# MeteoStation_ETH.net
KiCad netlist of a schematic drawn in Altium Designer
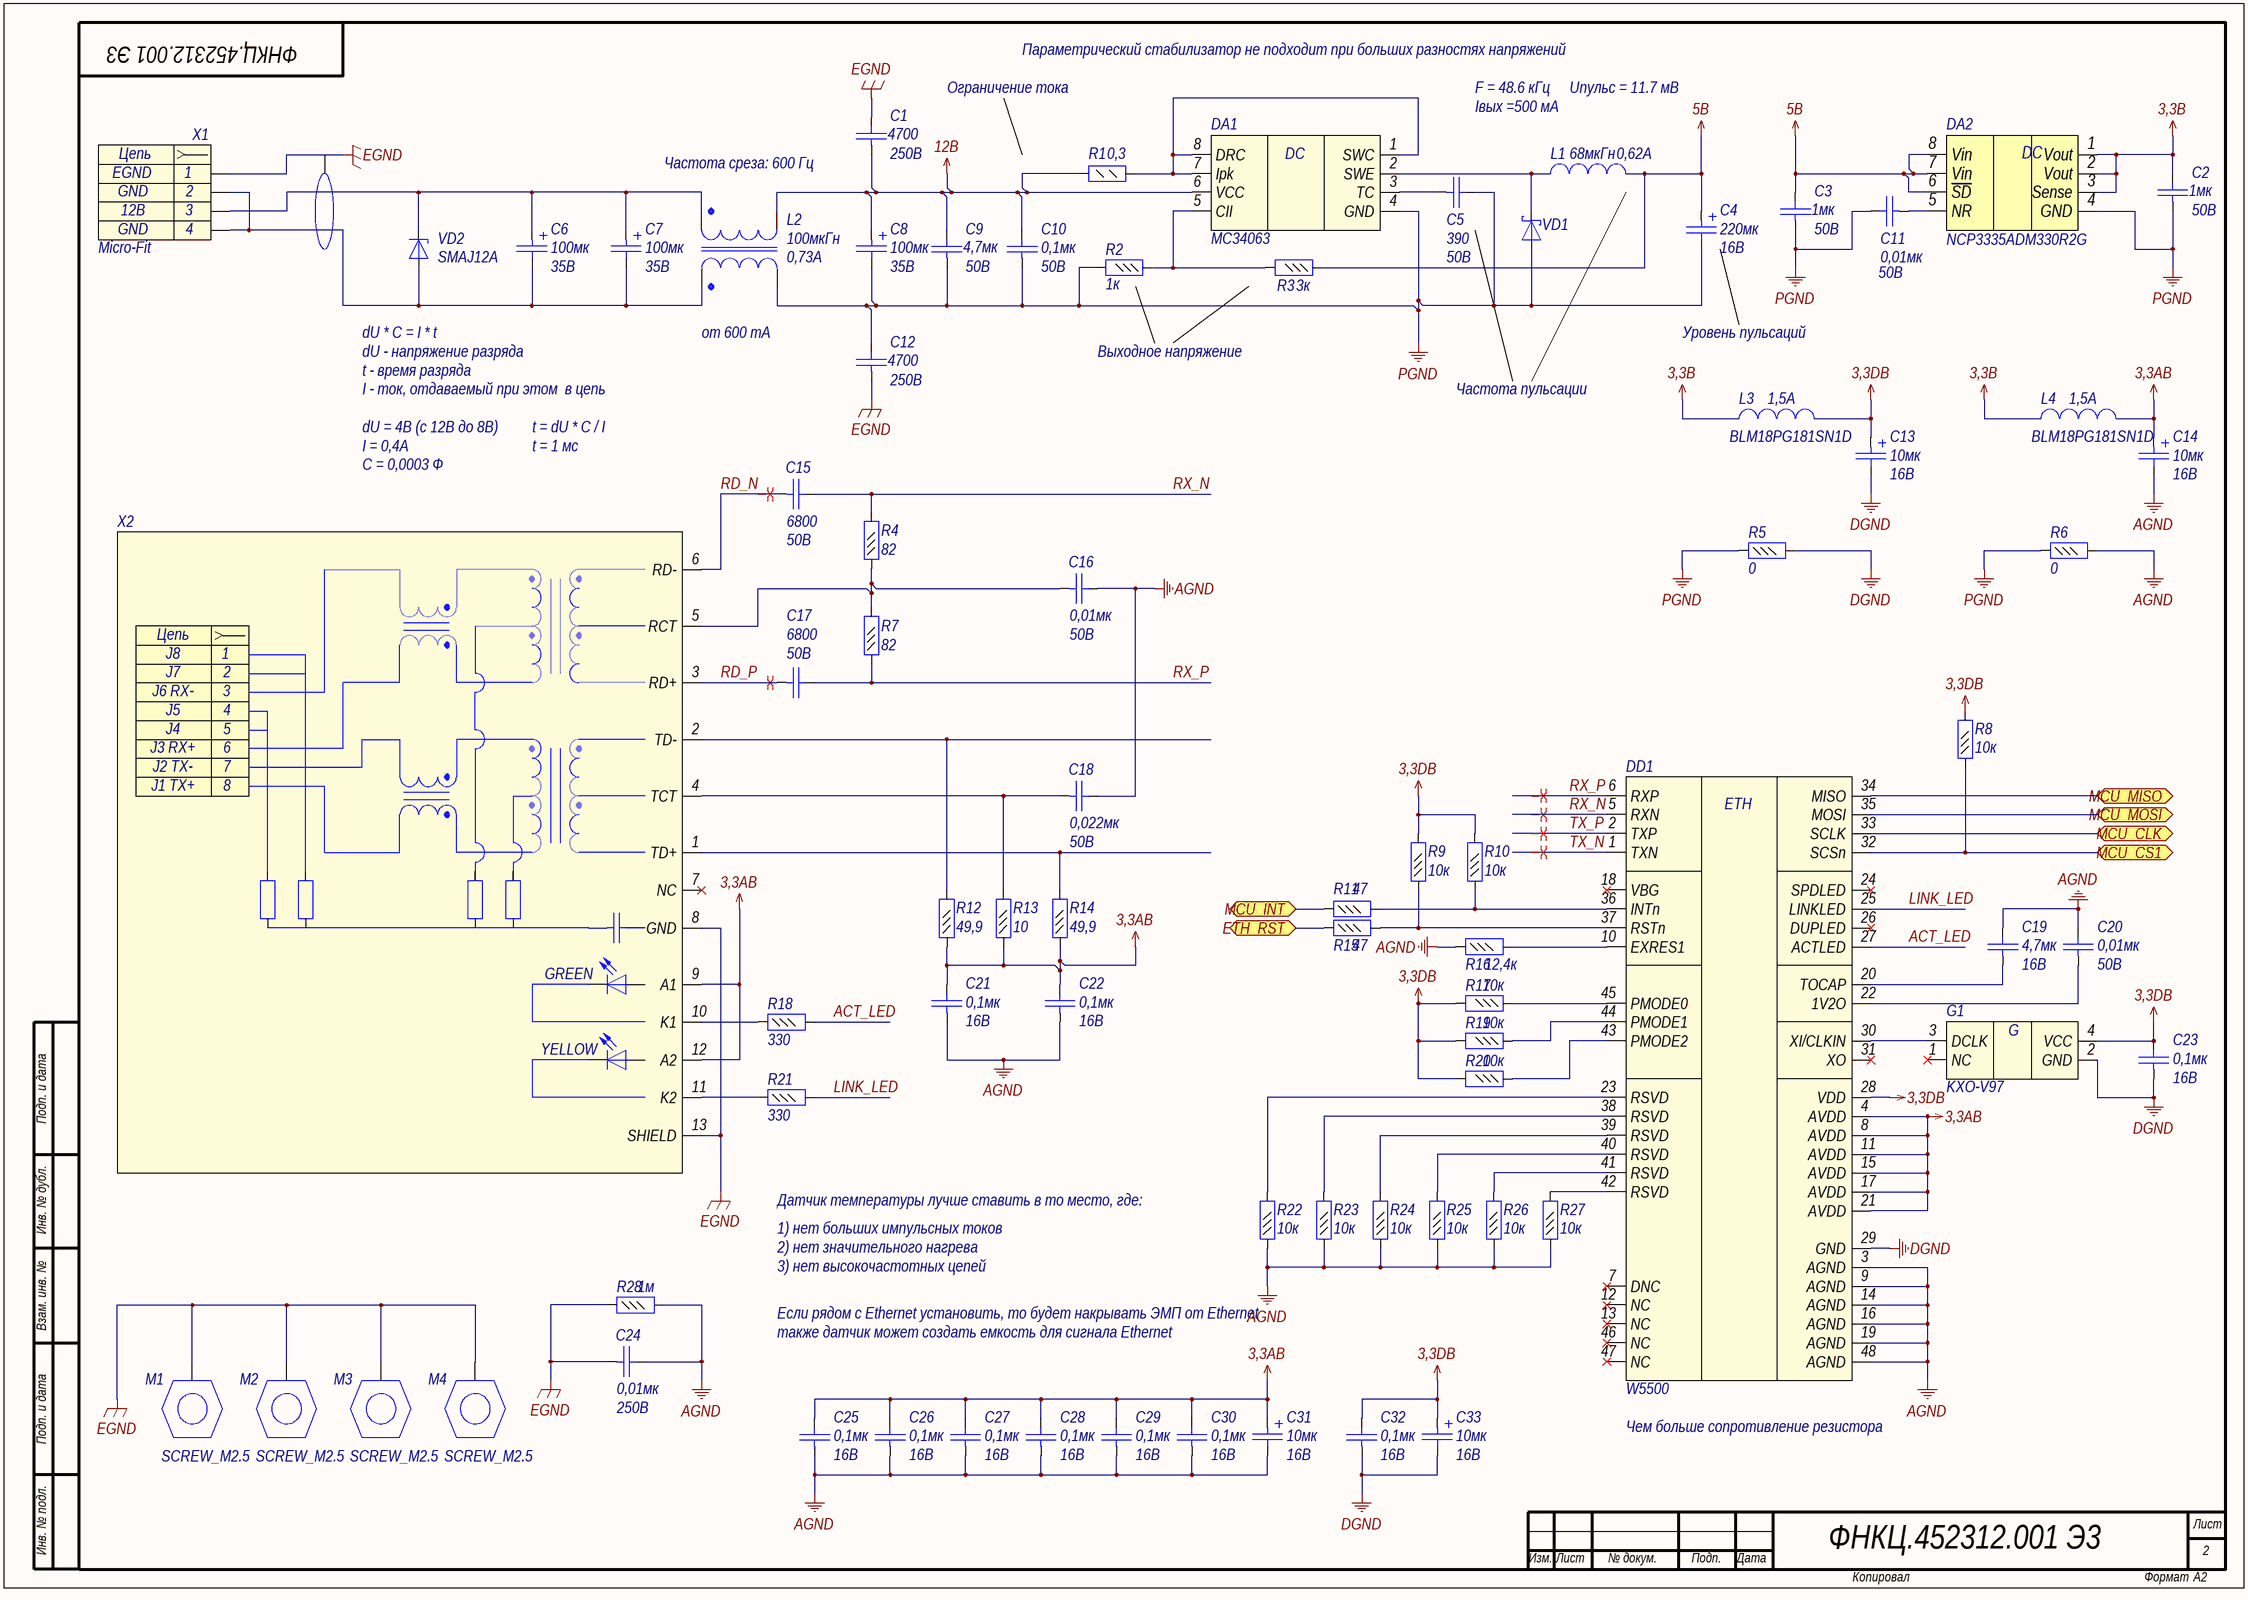
[diagram p0: MeteoStation_ETH.SchDoc]

(export (version "E")
  (design (tool "Eeschema 10.0.6"))
  (components
    (comp (ref "C1")
      (value "4700")
      (footprint "C0805")
      (description "Конденсатор")
      (fields
        (field (name "VOLTAGE") "250В")
        (field (name "PART NUMBER") "GRM21AR72E472KW")
        (field (name "Comment") "Capacitor")
      )
      (libsource (lib "MOP44") (part "Capacitor"))
    )
    (comp (ref "C2")
      (value "1мк")
      (footprint "C0603")
      (description "Конденсатор")
      (fields
        (field (name "VOLTAGE") "50B")
        (field (name "PART NUMBER") "GRM188R71C105KA12D**")
        (field (name "Comment") "Capacitor")
      )
      (libsource (lib "MOP44") (part "Capacitor"))
    )
    (comp (ref "C3")
      (value "1мк")
      (footprint "C0603")
      (description "Конденсатор")
      (fields
        (field (name "VOLTAGE") "50B")
        (field (name "PART NUMBER") "GRM188R71C105KA12D**")
        (field (name "Comment") "Capacitor")
      )
      (libsource (lib "MOP44") (part "Capacitor"))
    )
    (comp (ref "C4")
      (value "220мк")
      (footprint "K50-35(6.3X11)_MIRROR")
      (description "Конденсатор полярный")
      (fields
        (field (name "VOLTAGE") "16В")
        (field (name "PART NUMBER") "TKR221M1CE11")
        (field (name "Comment") "Capacitor_pol")
      )
      (libsource (lib "MOP44") (part "Capacitor_pol"))
    )
    (comp (ref "C5")
      (value "390")
      (footprint "C0603")
      (description "Конденсатор")
      (fields
        (field (name "VOLTAGE") "50B")
        (field (name "PART NUMBER") "GRM1885C1H391J")
        (field (name "Comment") "Capacitor")
      )
      (libsource (lib "MOP44") (part "Capacitor"))
    )
    (comp (ref "C6")
      (value "100мк")
      (footprint "K50-35(6.3X11)")
      (description "Конденсатор полярный")
      (fields
        (field (name "VOLTAGE") "35В")
        (field (name "PART NUMBER") "TKR101M1VE11")
        (field (name "Comment") "Capacitor_pol")
      )
      (libsource (lib "MOP44") (part "Capacitor_pol"))
    )
    (comp (ref "C7")
      (value "100мк")
      (footprint "K50-35(6.3X11)")
      (description "Конденсатор полярный")
      (fields
        (field (name "VOLTAGE") "35В")
        (field (name "PART NUMBER") "TKR101M1VE11")
        (field (name "Comment") "Capacitor_pol")
      )
      (libsource (lib "MOP44") (part "Capacitor_pol"))
    )
    (comp (ref "C8")
      (value "100мк")
      (footprint "K50-35(6.3X11)_MIRROR")
      (description "Конденсатор полярный")
      (fields
        (field (name "VOLTAGE") "35В")
        (field (name "PART NUMBER") "TKR101M1VE11")
        (field (name "Comment") "Capacitor_pol")
      )
      (libsource (lib "MOP44") (part "Capacitor_pol"))
    )
    (comp (ref "C9")
      (value "4,7мк")
      (footprint "C1206")
      (description "Конденсатор")
      (fields
        (field (name "VOLTAGE") "50В")
        (field (name "PART NUMBER") "GRM31CR71H475KA12L")
        (field (name "Comment") "Capacitor")
      )
      (libsource (lib "MOP44") (part "Capacitor"))
    )
    (comp (ref "C10")
      (value "0,1мк")
      (footprint "C0603")
      (description "Конденсатор")
      (fields
        (field (name "VOLTAGE") "50B")
        (field (name "PART NUMBER") "GRM188R71H104KA93D")
        (field (name "Comment") "Capacitor")
      )
      (libsource (lib "MOP44") (part "Capacitor"))
    )
    (comp (ref "C11")
      (value "0,01мк")
      (footprint "C0603")
      (description "Конденсатор")
      (fields
        (field (name "VOLTAGE") "50B")
        (field (name "PART NUMBER") "GRM188R71H103K")
        (field (name "Comment") "Capacitor")
      )
      (libsource (lib "MOP44") (part "Capacitor"))
    )
    (comp (ref "C12")
      (value "4700")
      (footprint "C0805")
      (description "Конденсатор")
      (fields
        (field (name "VOLTAGE") "250В")
        (field (name "PART NUMBER") "GRM21AR72E472KW")
        (field (name "Comment") "Capacitor")
      )
      (libsource (lib "MOP44") (part "Capacitor"))
    )
    (comp (ref "C13")
      (value "10мк")
      (footprint "TANTAL CASE A")
      (description "Конденсатор полярный")
      (fields
        (field (name "VOLTAGE") "16В")
        (field (name "PART NUMBER") "293D106X9016A2TE3")
        (field (name "Comment") "Capacitor_pol")
      )
      (libsource (lib "MOP44") (part "Capacitor_pol"))
    )
    (comp (ref "C14")
      (value "10мк")
      (footprint "TANTAL CASE A")
      (description "Конденсатор полярный")
      (fields
        (field (name "VOLTAGE") "16В")
        (field (name "PART NUMBER") "293D106X9016A2TE3")
        (field (name "Comment") "Capacitor_pol")
      )
      (libsource (lib "MOP44") (part "Capacitor_pol"))
    )
    (comp (ref "C15")
      (value "6800")
      (footprint "C0603")
      (description "Конденсатор")
      (fields
        (field (name "VOLTAGE") "50B")
        (field (name "PART NUMBER") "GRM188R71H682K")
        (field (name "Comment") "Capacitor")
      )
      (libsource (lib "MOP44") (part "Capacitor"))
    )
    (comp (ref "C16")
      (value "0,01мк")
      (footprint "C0402")
      (description "Конденсатор")
      (fields
        (field (name "VOLTAGE") "50B")
        (field (name "PART NUMBER") "GRM155R71H103K")
        (field (name "Comment") "Capacitor")
      )
      (libsource (lib "MOP44") (part "Capacitor"))
    )
    (comp (ref "C17")
      (value "6800")
      (footprint "C0603")
      (description "Конденсатор")
      (fields
        (field (name "VOLTAGE") "50B")
        (field (name "PART NUMBER") "GRM188R71H682K")
        (field (name "Comment") "Capacitor")
      )
      (libsource (lib "MOP44") (part "Capacitor"))
    )
    (comp (ref "C18")
      (value "0,022мк")
      (footprint "C0402")
      (description "Конденсатор")
      (fields
        (field (name "VOLTAGE") "50B")
        (field (name "PART NUMBER") "GRM155R71H223K")
        (field (name "Comment") "Capacitor")
      )
      (libsource (lib "MOP44") (part "Capacitor"))
    )
    (comp (ref "C19")
      (value "4,7мк")
      (footprint "C0805")
      (description "Конденсатор")
      (fields
        (field (name "VOLTAGE") "16В")
        (field (name "PART NUMBER") "GRM21BR71C475KA73L")
        (field (name "Comment") "Capacitor")
      )
      (libsource (lib "MOP44") (part "Capacitor"))
    )
    (comp (ref "C20")
      (value "0,01мк")
      (footprint "C0402")
      (description "Конденсатор")
      (fields
        (field (name "VOLTAGE") "50B")
        (field (name "PART NUMBER") "GRM155R71H103K")
        (field (name "Comment") "Capacitor")
      )
      (libsource (lib "MOP44") (part "Capacitor"))
    )
    (comp (ref "C21")
      (value "0,1мк")
      (footprint "C0402")
      (description "Конденсатор")
      (fields
        (field (name "VOLTAGE") "16B")
        (field (name "PART NUMBER") "GRM155R71C104KA88D ")
        (field (name "Comment") "Capacitor")
      )
      (libsource (lib "MOP44") (part "Capacitor"))
    )
    (comp (ref "C22")
      (value "0,1мк")
      (footprint "C0402")
      (description "Конденсатор")
      (fields
        (field (name "VOLTAGE") "16B")
        (field (name "PART NUMBER") "GRM155R71C104KA88D ")
        (field (name "Comment") "Capacitor")
      )
      (libsource (lib "MOP44") (part "Capacitor"))
    )
    (comp (ref "C23")
      (value "0,1мк")
      (footprint "C0402")
      (description "Конденсатор")
      (fields
        (field (name "VOLTAGE") "16B")
        (field (name "PART NUMBER") "GRM155R71C104KA88D ")
        (field (name "Comment") "Capacitor")
      )
      (libsource (lib "MOP44") (part "Capacitor"))
    )
    (comp (ref "C24")
      (value "0,01мк")
      (footprint "C0805")
      (description "Конденсатор")
      (fields
        (field (name "VOLTAGE") "250В")
        (field (name "PART NUMBER") "GRM21BR72E103K")
        (field (name "Comment") "Capacitor")
      )
      (libsource (lib "MOP44") (part "Capacitor"))
    )
    (comp (ref "C25")
      (value "0,1мк")
      (footprint "C0402")
      (description "Конденсатор")
      (fields
        (field (name "VOLTAGE") "16B")
        (field (name "PART NUMBER") "GRM155R71C104KA88D ")
        (field (name "Comment") "Capacitor")
      )
      (libsource (lib "MOP44") (part "Capacitor"))
    )
    (comp (ref "C26")
      (value "0,1мк")
      (footprint "C0402")
      (description "Конденсатор")
      (fields
        (field (name "VOLTAGE") "16B")
        (field (name "PART NUMBER") "GRM155R71C104KA88D ")
        (field (name "Comment") "Capacitor")
      )
      (libsource (lib "MOP44") (part "Capacitor"))
    )
    (comp (ref "C27")
      (value "0,1мк")
      (footprint "C0402")
      (description "Конденсатор")
      (fields
        (field (name "VOLTAGE") "16B")
        (field (name "PART NUMBER") "GRM155R71C104KA88D ")
        (field (name "Comment") "Capacitor")
      )
      (libsource (lib "MOP44") (part "Capacitor"))
    )
    (comp (ref "C28")
      (value "0,1мк")
      (footprint "C0402")
      (description "Конденсатор")
      (fields
        (field (name "VOLTAGE") "16B")
        (field (name "PART NUMBER") "GRM155R71C104KA88D ")
        (field (name "Comment") "Capacitor")
      )
      (libsource (lib "MOP44") (part "Capacitor"))
    )
    (comp (ref "C29")
      (value "0,1мк")
      (footprint "C0402")
      (description "Конденсатор")
      (fields
        (field (name "VOLTAGE") "16B")
        (field (name "PART NUMBER") "GRM155R71C104KA88D ")
        (field (name "Comment") "Capacitor")
      )
      (libsource (lib "MOP44") (part "Capacitor"))
    )
    (comp (ref "C30")
      (value "0,1мк")
      (footprint "C0402")
      (description "Конденсатор")
      (fields
        (field (name "VOLTAGE") "16B")
        (field (name "PART NUMBER") "GRM155R71C104KA88D ")
        (field (name "Comment") "Capacitor")
      )
      (libsource (lib "MOP44") (part "Capacitor"))
    )
    (comp (ref "C31")
      (value "10мк")
      (footprint "TANTAL CASE A")
      (description "Конденсатор полярный")
      (fields
        (field (name "VOLTAGE") "16В")
        (field (name "PART NUMBER") "293D106X9016A2TE3")
        (field (name "Comment") "Capacitor_pol")
      )
      (libsource (lib "MOP44") (part "Capacitor_pol"))
    )
    (comp (ref "C32")
      (value "0,1мк")
      (footprint "C0402")
      (description "Конденсатор")
      (fields
        (field (name "VOLTAGE") "16B")
        (field (name "PART NUMBER") "GRM155R71C104KA88D ")
        (field (name "Comment") "Capacitor")
      )
      (libsource (lib "MOP44") (part "Capacitor"))
    )
    (comp (ref "C33")
      (value "10мк")
      (footprint "TANTAL CASE A")
      (description "Конденсатор полярный")
      (fields
        (field (name "VOLTAGE") "16В")
        (field (name "PART NUMBER") "293D106X9016A2TE3")
        (field (name "Comment") "Capacitor_pol")
      )
      (libsource (lib "MOP44") (part "Capacitor_pol"))
    )
    (comp (ref "DA1")
      (value "MC34063")
      (footprint "SO8")
      (description "1.5 A, Step-Up/Down/  Inverting Switching  Regulators")
      (fields (field (name "PART NUMBER") "MC34063ADR2G") (field (name "MANUFACTURER") "ON Semiconductor"))
      (libsource (lib "MOP44") (part "MC34063"))
    )
    (comp (ref "DA2")
      (value "NCP3335ADM330R2G")
      (footprint "MICRO8")
      (description "Линейный стабилизатор напряжения, фиксированный выход")
      (fields (field (name "MANUFACTURER") "ON Semiconductor"))
      (libsource (lib "MOP44") (part "NCP3335ADM330R2G"))
    )
    (comp (ref "DD1")
      (value "~")
      (footprint "LQFP48")
      (description "Ethernet - SPI")
      (fields (field (name "PART NUMBER") "W5500"))
      (libsource (lib "MOP44") (part "W5500"))
    )
    (comp (ref "G1")
      (value "KXO")
      (footprint "QSMD7x5.2x1.8")
      (description "Кварц. генер. 32.768 МГц (HCMOS/TTL)")
      (fields (field (name "PART NUMBER") "KXO-V97"))
      (libsource (lib "MOP44") (part "KXO"))
    )
    (comp (ref "L1")
      (value "68мкГн")
      (footprint "SDR0604")
      (description "EMI Suppression Filter")
      (fields
        (field (name "RATED CURRENT") "0,62A")
        (field (name "PART NUMBER") "SDR0604- 680KL")
        (field (name "Comment") "Inductor")
      )
      (libsource (lib "MOP44") (part "Inductor"))
    )
    (comp (ref "L2")
      (value "100мкГн")
      (footprint "SRF0703")
      (description "Синфазный дроссель")
      (fields
        (field (name "RATED CURRENT") "0,73A")
        (field (name "PART NUMBER") "SRF0703-101M")
        (field (name "Comment") "Dual-Winding Inductor")
      )
      (libsource (lib "MOP44") (part "Dual-Winding Inductor"))
    )
    (comp (ref "L3")
      (value "Inductor")
      (footprint "L0603")
      (description "EMI Suppression Filter")
      (fields (field (name "RATED CURRENT") "1,5A") (field (name "PART NUMBER") "BLM18PG181SN1D"))
      (libsource (lib "MOP44") (part "Inductor"))
    )
    (comp (ref "L4")
      (value "Inductor")
      (footprint "L0603")
      (description "EMI Suppression Filter")
      (fields (field (name "RATED CURRENT") "1,5A") (field (name "PART NUMBER") "BLM18PG181SN1D"))
      (libsource (lib "MOP44") (part "Inductor"))
    )
    (comp (ref "M1") (value "SCREW_M2.5") (footprint "HOLE2.5") (libsource (lib "MOP44") (part "SCREW_M2.5")))
    (comp (ref "M2") (value "SCREW_M2.5") (footprint "HOLE2.5") (libsource (lib "MOP44") (part "SCREW_M2.5")))
    (comp (ref "M3") (value "SCREW_M2.5") (footprint "HOLE2.5") (libsource (lib "MOP44") (part "SCREW_M2.5")))
    (comp (ref "M4") (value "SCREW_M2.5") (footprint "HOLE2.5") (libsource (lib "MOP44") (part "SCREW_M2.5")))
    (comp (ref "R1")
      (value "0,3")
      (footprint "R0805")
      (description "Резистор")
      (fields (field (name "PART NUMBER") "RC0805FR-0749R9L") (field (name "POWER") "0,125Вт"))
      (libsource (lib "MOP44") (part "Resistor_0,125Вт"))
    )
    (comp (ref "R2")
      (value "1к")
      (footprint "R0603")
      (description "Резистор")
      (fields (field (name "PART NUMBER") "RC0603FR-071KL") (field (name "POWER") "0,062Вт"))
      (libsource (lib "MOP44") (part "Resistor_0,062Вт"))
    )
    (comp (ref "R3")
      (value "3к")
      (footprint "R0603")
      (description "Резистор")
      (fields (field (name "PART NUMBER") "RC0603FR-073KL") (field (name "POWER") "0,062Вт"))
      (libsource (lib "MOP44") (part "Resistor_0,062Вт"))
    )
    (comp (ref "R4")
      (value "82")
      (footprint "R0402")
      (description "Резистор")
      (fields (field (name "PART NUMBER") "RC0402FR-0782RL") (field (name "POWER") "0,062Вт"))
      (libsource (lib "") (part "Resistor_0,062Вт_2"))
    )
    (comp (ref "R5")
      (value "0")
      (footprint "R0603")
      (description "Резистор")
      (fields (field (name "PART NUMBER") "RC0603FR-070RL") (field (name "POWER") "0,062Вт"))
      (libsource (lib "") (part "Resistor_0,062Вт_1"))
    )
    (comp (ref "R6")
      (value "0")
      (footprint "R0603")
      (description "Резистор")
      (fields (field (name "PART NUMBER") "RC0603FR-070RL") (field (name "POWER") "0,062Вт"))
      (libsource (lib "") (part "Resistor_0,062Вт_1"))
    )
    (comp (ref "R7")
      (value "82")
      (footprint "R0402")
      (description "Резистор")
      (fields (field (name "PART NUMBER") "RC0402FR-0782RL") (field (name "POWER") "0,062Вт"))
      (libsource (lib "") (part "Resistor_0,062Вт_2"))
    )
    (comp (ref "R8")
      (value "10к")
      (footprint "R0402")
      (description "Резистор")
      (fields (field (name "PART NUMBER") "RC0402FR-0710KL") (field (name "POWER") "0,062Вт"))
      (libsource (lib "") (part "Resistor_0,062Вт_2"))
    )
    (comp (ref "R9")
      (value "10к")
      (footprint "R0402")
      (description "Резистор")
      (fields (field (name "PART NUMBER") "RC0402FR-0710KL") (field (name "POWER") "0,062Вт"))
      (libsource (lib "") (part "Resistor_0,062Вт_2"))
    )
    (comp (ref "R10")
      (value "10к")
      (footprint "R0402")
      (description "Резистор")
      (fields (field (name "PART NUMBER") "RC0402FR-0710KL") (field (name "POWER") "0,062Вт"))
      (libsource (lib "") (part "Resistor_0,062Вт_2"))
    )
    (comp (ref "R11")
      (value "47")
      (footprint "R0402")
      (description "Резистор")
      (fields (field (name "PART NUMBER") "RC0402FR-0747RL") (field (name "POWER") "0,062Вт"))
      (libsource (lib "") (part "Resistor_0,062Вт_1"))
    )
    (comp (ref "R12")
      (value "49,9")
      (footprint "R0402")
      (description "Резистор")
      (fields (field (name "PART NUMBER") "RC0402FR-0749R9L") (field (name "POWER") "0,062Вт"))
      (libsource (lib "") (part "Resistor_0,062Вт_2"))
    )
    (comp (ref "R13")
      (value "10")
      (footprint "R0402")
      (description "Резистор")
      (fields (field (name "PART NUMBER") "RC0402FR-0710RL") (field (name "POWER") "0,062Вт"))
      (libsource (lib "") (part "Resistor_0,062Вт_2"))
    )
    (comp (ref "R14")
      (value "49,9")
      (footprint "R0402")
      (description "Резистор")
      (fields (field (name "PART NUMBER") "RC0402FR-0749R9L") (field (name "POWER") "0,062Вт"))
      (libsource (lib "") (part "Resistor_0,062Вт_2"))
    )
    (comp (ref "R15")
      (value "47")
      (footprint "R0402")
      (description "Резистор")
      (fields (field (name "PART NUMBER") "RC0402FR-0747RL") (field (name "POWER") "0,062Вт"))
      (libsource (lib "") (part "Resistor_0,062Вт_1"))
    )
    (comp (ref "R16")
      (value "12,4к")
      (footprint "R0603")
      (description "Резистор")
      (fields (field (name "PART NUMBER") "RC0603FR-0712K4L") (field (name "POWER") "0,062Вт"))
      (libsource (lib "") (part "Resistor_0,062Вт_1"))
    )
    (comp (ref "R17")
      (value "10к")
      (footprint "R0402")
      (description "Резистор")
      (fields (field (name "PART NUMBER") "RC0402FR-0710KL") (field (name "POWER") "0,062Вт"))
      (libsource (lib "MOP44") (part "Resistor_0,062Вт"))
    )
    (comp (ref "R18")
      (value "330")
      (footprint "R0402")
      (description "Резистор")
      (fields (field (name "PART NUMBER") "RC0402FR-07330RL") (field (name "POWER") "0,062Вт"))
      (libsource (lib "") (part "Resistor_0,062Вт_1"))
    )
    (comp (ref "R19")
      (value "10к")
      (footprint "R0402")
      (description "Резистор")
      (fields (field (name "PART NUMBER") "RC0402FR-0710KL") (field (name "POWER") "0,062Вт"))
      (libsource (lib "MOP44") (part "Resistor_0,062Вт"))
    )
    (comp (ref "R20")
      (value "10к")
      (footprint "R0402")
      (description "Резистор")
      (fields (field (name "PART NUMBER") "RC0402FR-0710KL") (field (name "POWER") "0,062Вт"))
      (libsource (lib "MOP44") (part "Resistor_0,062Вт"))
    )
    (comp (ref "R21")
      (value "330")
      (footprint "R0402")
      (description "Резистор")
      (fields (field (name "PART NUMBER") "RC0402FR-07330RL") (field (name "POWER") "0,062Вт"))
      (libsource (lib "") (part "Resistor_0,062Вт_1"))
    )
    (comp (ref "R22")
      (value "10к")
      (footprint "R0402")
      (description "Резистор")
      (fields (field (name "PART NUMBER") "RC0402FR-0710KL") (field (name "POWER") "0,062Вт"))
      (libsource (lib "") (part "Resistor_0,062Вт_2"))
    )
    (comp (ref "R23")
      (value "10к")
      (footprint "R0402")
      (description "Резистор")
      (fields (field (name "PART NUMBER") "RC0402FR-0710KL") (field (name "POWER") "0,062Вт"))
      (libsource (lib "") (part "Resistor_0,062Вт_2"))
    )
    (comp (ref "R24")
      (value "10к")
      (footprint "R0402")
      (description "Резистор")
      (fields (field (name "PART NUMBER") "RC0402FR-0710KL") (field (name "POWER") "0,062Вт"))
      (libsource (lib "") (part "Resistor_0,062Вт_2"))
    )
    (comp (ref "R25")
      (value "10к")
      (footprint "R0402")
      (description "Резистор")
      (fields (field (name "PART NUMBER") "RC0402FR-0710KL") (field (name "POWER") "0,062Вт"))
      (libsource (lib "") (part "Resistor_0,062Вт_2"))
    )
    (comp (ref "R26")
      (value "10к")
      (footprint "R0402")
      (description "Резистор")
      (fields (field (name "PART NUMBER") "RC0402FR-0710KL") (field (name "POWER") "0,062Вт"))
      (libsource (lib "") (part "Resistor_0,062Вт_2"))
    )
    (comp (ref "R27")
      (value "10к")
      (footprint "R0402")
      (description "Резистор")
      (fields (field (name "PART NUMBER") "RC0402FR-0710KL") (field (name "POWER") "0,062Вт"))
      (libsource (lib "") (part "Resistor_0,062Вт_2"))
    )
    (comp (ref "R28")
      (value "1м")
      (footprint "R0603")
      (description "Резистор")
      (fields (field (name "PART NUMBER") "RC0603FR-071ML") (field (name "POWER") "0,062Вт"))
      (libsource (lib "") (part "Resistor_0,062Вт_1"))
    )
    (comp (ref "VD1")
      (value "DiodeSchottky")
      (footprint "SOD-323")
      (description "Диод Шоттки")
      (fields (field (name "PART NUMBER") "PMEG4010BEA.115"))
      (libsource (lib "MOP44") (part "DiodeSchottky"))
    )
    (comp (ref "VD2")
      (value "DiodeZener")
      (footprint "SMA")
      (description "Cтабилитрон (лавинный выпрямительный диод) односторонний")
      (fields (field (name "PART NUMBER") "SMAJ12A"))
      (libsource (lib "MOP44") (part "DiodeZener"))
    )
    (comp (ref "X1")
      (value "Micro-Fit")
      (footprint "43045-0400")
      (description "Разъем - 4 конт. розетка")
      (fields (field (name "PART NUMBER") "43045-0400"))
      (libsource (lib "MOP44") (part "Header_4_sct"))
    )
    (comp (ref "X2")
      (value "HR911105A")
      (footprint "RJ45_HANRUN")
      (description "Разъем - 6 конт. вилка")
      (libsource (lib "MOP44") (part "HR911105A"))
    )
  )
  (nets
    (net (code "1") (name "/ACT_LED") (class "Default")
      (node (ref "DD1") (pin "27") (pinfunction "ACTLED_27") (pintype "power_in"))
      (node (ref "R18") (pin "2") (pinfunction "2_2") (pintype "passive"))
    )
    (net (code "2") (name "/ETH_RST") (class "Default")
      (node (ref "R15") (pin "1") (pinfunction "1_1") (pintype "passive"))
    )
    (net (code "3") (name "/LINK_LED") (class "Default")
      (node (ref "DD1") (pin "25") (pinfunction "LINKLED_25") (pintype "power_in"))
      (node (ref "R21") (pin "2") (pinfunction "2_2") (pintype "passive"))
    )
    (net (code "4") (name "/MCU_CLK") (class "Default")
      (node (ref "DD1") (pin "33") (pinfunction "SCLK_33") (pintype "power_in"))
    )
    (net (code "5") (name "/MCU_CS1") (class "Default")
      (node (ref "DD1") (pin "32") (pinfunction "SCSn_32") (pintype "power_in"))
      (node (ref "R8") (pin "1") (pinfunction "1_1") (pintype "passive"))
    )
    (net (code "6") (name "/MCU_INT") (class "Default")
      (node (ref "R11") (pin "1") (pinfunction "1_1") (pintype "passive"))
    )
    (net (code "7") (name "/MCU_MISO") (class "Default")
      (node (ref "DD1") (pin "34") (pinfunction "MISO_34") (pintype "power_in"))
    )
    (net (code "8") (name "/MCU_MOSI") (class "Default")
      (node (ref "DD1") (pin "35") (pinfunction "MOSI_35") (pintype "power_in"))
    )
    (net (code "9") (name "/RD_N") (class "Default")
      (node (ref "C15") (pin "1") (pinfunction "1_1") (pintype "passive"))
      (node (ref "X2") (pin "6") (pinfunction "RD-_6") (pintype "passive"))
    )
    (net (code "10") (name "/RD_P") (class "Default")
      (node (ref "C17") (pin "1") (pinfunction "1_1") (pintype "passive"))
      (node (ref "X2") (pin "3") (pinfunction "RD+_3") (pintype "passive"))
    )
    (net (code "11") (name "/RX_N") (class "Default")
      (node (ref "C15") (pin "2") (pinfunction "2_2") (pintype "passive"))
      (node (ref "DD1") (pin "5") (pinfunction "RXN_5") (pintype "power_in"))
      (node (ref "R4") (pin "2") (pinfunction "2_2") (pintype "passive"))
    )
    (net (code "12") (name "/RX_P") (class "Default")
      (node (ref "C17") (pin "2") (pinfunction "2_2") (pintype "passive"))
      (node (ref "DD1") (pin "6") (pinfunction "RXP_6") (pintype "power_in"))
      (node (ref "R7") (pin "1") (pinfunction "1_1") (pintype "passive"))
    )
    (net (code "13") (name "/TX_N") (class "Default")
      (node (ref "DD1") (pin "1") (pinfunction "TXN_1") (pintype "power_in"))
    )
    (net (code "14") (name "/TX_P") (class "Default")
      (node (ref "DD1") (pin "2") (pinfunction "TXP_2") (pintype "power_in"))
    )
    (net (code "15") (name "3,3AB") (class "Default")
      (node (ref "C14") (pin "1") (pinfunction "1_1") (pintype "passive"))
      (node (ref "C21") (pin "2") (pinfunction "2_2") (pintype "passive"))
      (node (ref "C22") (pin "2") (pinfunction "2_2") (pintype "passive"))
      (node (ref "C25") (pin "2") (pinfunction "2_2") (pintype "passive"))
      (node (ref "C26") (pin "2") (pinfunction "2_2") (pintype "passive"))
      (node (ref "C27") (pin "2") (pinfunction "2_2") (pintype "passive"))
      (node (ref "C28") (pin "2") (pinfunction "2_2") (pintype "passive"))
      (node (ref "C29") (pin "2") (pinfunction "2_2") (pintype "passive"))
      (node (ref "C30") (pin "2") (pinfunction "2_2") (pintype "passive"))
      (node (ref "C31") (pin "1") (pinfunction "1_1") (pintype "passive"))
      (node (ref "DD1") (pin "11") (pinfunction "AVDD_11") (pintype "power_in"))
      (node (ref "DD1") (pin "15") (pinfunction "AVDD_15") (pintype "power_in"))
      (node (ref "DD1") (pin "17") (pinfunction "AVDD_17") (pintype "power_in"))
      (node (ref "DD1") (pin "21") (pinfunction "AVDD_21") (pintype "power_in"))
      (node (ref "DD1") (pin "4") (pinfunction "AVDD_4") (pintype "power_in"))
      (node (ref "DD1") (pin "8") (pinfunction "AVDD_8") (pintype "power_in"))
      (node (ref "L4") (pin "2") (pinfunction "2_2") (pintype "passive"))
      (node (ref "R12") (pin "1") (pinfunction "1_1") (pintype "passive"))
      (node (ref "R13") (pin "1") (pinfunction "1_1") (pintype "passive"))
      (node (ref "R14") (pin "1") (pinfunction "1_1") (pintype "passive"))
      (node (ref "X2") (pin "12") (pinfunction "A2_12") (pintype "passive"))
      (node (ref "X2") (pin "9") (pinfunction "A1_9") (pintype "passive"))
    )
    (net (code "16") (name "3,3B") (class "Default")
      (node (ref "C2") (pin "2") (pinfunction "2_2") (pintype "passive"))
      (node (ref "DA2") (pin "1") (pinfunction "Vout_1") (pintype "passive"))
      (node (ref "DA2") (pin "2") (pinfunction "Vout_2") (pintype "passive"))
      (node (ref "DA2") (pin "3") (pinfunction "Sense_3") (pintype "passive"))
      (node (ref "L3") (pin "1") (pinfunction "1_1") (pintype "passive"))
      (node (ref "L4") (pin "1") (pinfunction "1_1") (pintype "passive"))
    )
    (net (code "17") (name "3,3DB") (class "Default")
      (node (ref "C13") (pin "1") (pinfunction "1_1") (pintype "passive"))
      (node (ref "C23") (pin "2") (pinfunction "2_2") (pintype "passive"))
      (node (ref "C32") (pin "2") (pinfunction "2_2") (pintype "passive"))
      (node (ref "C33") (pin "1") (pinfunction "1_1") (pintype "passive"))
      (node (ref "DD1") (pin "28") (pinfunction "VDD_28") (pintype "power_in"))
      (node (ref "G1") (pin "4") (pinfunction "VCC_4") (pintype "power_in"))
      (node (ref "L3") (pin "2") (pinfunction "2_2") (pintype "passive"))
      (node (ref "R10") (pin "2") (pinfunction "2_2") (pintype "passive"))
      (node (ref "R17") (pin "2") (pinfunction "2_2") (pintype "passive"))
      (node (ref "R19") (pin "2") (pinfunction "2_2") (pintype "passive"))
      (node (ref "R20") (pin "2") (pinfunction "2_2") (pintype "passive"))
      (node (ref "R8") (pin "2") (pinfunction "2_2") (pintype "passive"))
      (node (ref "R9") (pin "2") (pinfunction "2_2") (pintype "passive"))
    )
    (net (code "18") (name "5B") (class "Default")
      (node (ref "C3") (pin "2") (pinfunction "2_2") (pintype "passive"))
      (node (ref "C4") (pin "1") (pinfunction "1_1") (pintype "passive"))
      (node (ref "DA2") (pin "6") (pinfunction "~{SD}_6") (pintype "passive"))
      (node (ref "DA2") (pin "7") (pinfunction "Vin_7") (pintype "passive"))
      (node (ref "DA2") (pin "8") (pinfunction "Vin_8") (pintype "passive"))
      (node (ref "L1") (pin "2") (pinfunction "2_2") (pintype "passive"))
      (node (ref "R3") (pin "1") (pinfunction "1_1") (pintype "passive"))
    )
    (net (code "19") (name "12B") (class "Default")
      (node (ref "C1") (pin "1") (pinfunction "1_1") (pintype "passive"))
      (node (ref "C10") (pin "2") (pinfunction "2_2") (pintype "passive"))
      (node (ref "C8") (pin "1") (pinfunction "1_1") (pintype "passive"))
      (node (ref "C9") (pin "2") (pinfunction "2_2") (pintype "passive"))
      (node (ref "DA1") (pin "6") (pinfunction "VCC_6") (pintype "power_in"))
      (node (ref "L2") (pin "4") (pintype "passive"))
      (node (ref "R1") (pin "1") (pinfunction "1_1") (pintype "passive"))
    )
    (net (code "20") (name "AGND") (class "Default")
      (node (ref "C14") (pin "2") (pinfunction "2_2") (pintype "passive"))
      (node (ref "C16") (pin "2") (pinfunction "2_2") (pintype "passive"))
      (node (ref "C18") (pin "2") (pinfunction "2_2") (pintype "passive"))
      (node (ref "C19") (pin "2") (pinfunction "2_2") (pintype "passive"))
      (node (ref "C20") (pin "2") (pinfunction "2_2") (pintype "passive"))
      (node (ref "C21") (pin "1") (pinfunction "1_1") (pintype "passive"))
      (node (ref "C22") (pin "1") (pinfunction "1_1") (pintype "passive"))
      (node (ref "C24") (pin "2") (pinfunction "2_2") (pintype "passive"))
      (node (ref "C25") (pin "1") (pinfunction "1_1") (pintype "passive"))
      (node (ref "C26") (pin "1") (pinfunction "1_1") (pintype "passive"))
      (node (ref "C27") (pin "1") (pinfunction "1_1") (pintype "passive"))
      (node (ref "C28") (pin "1") (pinfunction "1_1") (pintype "passive"))
      (node (ref "C29") (pin "1") (pinfunction "1_1") (pintype "passive"))
      (node (ref "C30") (pin "1") (pinfunction "1_1") (pintype "passive"))
      (node (ref "C31") (pin "2") (pinfunction "2_2") (pintype "passive"))
      (node (ref "DD1") (pin "14") (pinfunction "AGND_14") (pintype "power_in"))
      (node (ref "DD1") (pin "16") (pinfunction "AGND_16") (pintype "power_in"))
      (node (ref "DD1") (pin "19") (pinfunction "AGND_19") (pintype "power_in"))
      (node (ref "DD1") (pin "3") (pinfunction "AGND_3") (pintype "power_in"))
      (node (ref "DD1") (pin "48") (pinfunction "AGND_48") (pintype "power_in"))
      (node (ref "DD1") (pin "9") (pinfunction "AGND_9") (pintype "power_in"))
      (node (ref "R16") (pin "1") (pinfunction "1_1") (pintype "passive"))
      (node (ref "R22") (pin "1") (pinfunction "1_1") (pintype "passive"))
      (node (ref "R23") (pin "1") (pinfunction "1_1") (pintype "passive"))
      (node (ref "R24") (pin "1") (pinfunction "1_1") (pintype "passive"))
      (node (ref "R25") (pin "1") (pinfunction "1_1") (pintype "passive"))
      (node (ref "R26") (pin "1") (pinfunction "1_1") (pintype "passive"))
      (node (ref "R27") (pin "1") (pinfunction "1_1") (pintype "passive"))
      (node (ref "R28") (pin "2") (pinfunction "2_2") (pintype "passive"))
      (node (ref "R6") (pin "2") (pinfunction "2_2") (pintype "passive"))
    )
    (net (code "21") (name "DGND") (class "Default")
      (node (ref "C13") (pin "2") (pinfunction "2_2") (pintype "passive"))
      (node (ref "C23") (pin "1") (pinfunction "1_1") (pintype "passive"))
      (node (ref "C32") (pin "1") (pinfunction "1_1") (pintype "passive"))
      (node (ref "C33") (pin "2") (pinfunction "2_2") (pintype "passive"))
      (node (ref "DD1") (pin "29") (pinfunction "GND_29") (pintype "power_in"))
      (node (ref "G1") (pin "2") (pinfunction "GND_2") (pintype "power_in"))
      (node (ref "R5") (pin "2") (pinfunction "2_2") (pintype "passive"))
    )
    (net (code "22") (name "EGND") (class "Default")
      (node (ref "C1") (pin "2") (pinfunction "2_2") (pintype "passive"))
      (node (ref "C12") (pin "1") (pinfunction "1_1") (pintype "passive"))
      (node (ref "C24") (pin "1") (pinfunction "1_1") (pintype "passive"))
      (node (ref "M1") (pin "1") (pinfunction "1_1") (pintype "passive"))
      (node (ref "M2") (pin "1") (pinfunction "1_1") (pintype "passive"))
      (node (ref "M3") (pin "1") (pinfunction "1_1") (pintype "passive"))
      (node (ref "M4") (pin "1") (pinfunction "1_1") (pintype "passive"))
      (node (ref "R28") (pin "1") (pinfunction "1_1") (pintype "passive"))
      (node (ref "X1") (pin "1") (pinfunction "1_1") (pintype "passive"))
      (node (ref "X2") (pin "13") (pinfunction "SHIELD_13") (pintype "passive"))
      (node (ref "X2") (pin "8") (pinfunction "GND_8") (pintype "passive"))
    )
    (net (code "23") (name "Net-(DA1-CII)") (class "Default")
      (node (ref "DA1") (pin "5") (pinfunction "CII_5") (pintype "power_in"))
      (node (ref "R2") (pin "1") (pinfunction "1_1") (pintype "passive"))
      (node (ref "R3") (pin "2") (pinfunction "2_2") (pintype "passive"))
    )
    (net (code "24") (name "Net-(DA1-DRC)") (class "Default")
      (node (ref "DA1") (pin "1") (pinfunction "SWC_1") (pintype "power_in"))
      (node (ref "DA1") (pin "7") (pinfunction "Ipk_7") (pintype "power_in"))
      (node (ref "DA1") (pin "8") (pinfunction "DRC_8") (pintype "power_in"))
      (node (ref "R1") (pin "2") (pinfunction "2_2") (pintype "passive"))
    )
    (net (code "25") (name "Net-(DA1-SWE)") (class "Default")
      (node (ref "DA1") (pin "2") (pinfunction "SWE_2") (pintype "power_in"))
      (node (ref "L1") (pin "1") (pinfunction "1_1") (pintype "passive"))
      (node (ref "VD1") (pin "1") (pinfunction "K_1") (pintype "passive"))
    )
    (net (code "26") (name "Net-(DA1-TC)") (class "Default")
      (node (ref "C5") (pin "1") (pinfunction "1_1") (pintype "passive"))
      (node (ref "DA1") (pin "3") (pinfunction "TC_3") (pintype "power_in"))
    )
    (net (code "27") (name "Net-(DA2-NR)") (class "Default")
      (node (ref "C11") (pin "1") (pinfunction "1_1") (pintype "passive"))
      (node (ref "DA2") (pin "5") (pinfunction "NR_5") (pintype "passive"))
    )
    (net (code "28") (name "Net-(DD1-1V2O)") (class "Default")
      (node (ref "C20") (pin "1") (pinfunction "1_1") (pintype "passive"))
      (node (ref "DD1") (pin "22") (pinfunction "1V2O_22") (pintype "power_in"))
    )
    (net (code "29") (name "Net-(DD1-EXRES1)") (class "Default")
      (node (ref "DD1") (pin "10") (pinfunction "EXRES1_10") (pintype "power_in"))
      (node (ref "R16") (pin "2") (pinfunction "2_2") (pintype "passive"))
    )
    (net (code "30") (name "Net-(DD1-INTn)") (class "Default")
      (node (ref "DD1") (pin "36") (pinfunction "INTn_36") (pintype "power_in"))
      (node (ref "R10") (pin "1") (pinfunction "1_1") (pintype "passive"))
      (node (ref "R11") (pin "2") (pinfunction "2_2") (pintype "passive"))
    )
    (net (code "31") (name "Net-(DD1-PMODE0)") (class "Default")
      (node (ref "DD1") (pin "45") (pinfunction "PMODE0_45") (pintype "power_in"))
      (node (ref "R17") (pin "1") (pinfunction "1_1") (pintype "passive"))
    )
    (net (code "32") (name "Net-(DD1-PMODE1)") (class "Default")
      (node (ref "DD1") (pin "44") (pinfunction "PMODE1_44") (pintype "power_in"))
      (node (ref "R19") (pin "1") (pinfunction "1_1") (pintype "passive"))
    )
    (net (code "33") (name "Net-(DD1-PMODE2)") (class "Default")
      (node (ref "DD1") (pin "43") (pinfunction "PMODE2_43") (pintype "power_in"))
      (node (ref "R20") (pin "1") (pinfunction "1_1") (pintype "passive"))
    )
    (net (code "34") (name "Net-(DD1-RSTn)") (class "Default")
      (node (ref "DD1") (pin "37") (pinfunction "RSTn_37") (pintype "power_in"))
      (node (ref "R15") (pin "2") (pinfunction "2_2") (pintype "passive"))
      (node (ref "R9") (pin "1") (pinfunction "1_1") (pintype "passive"))
    )
    (net (code "35") (name "Net-(DD1-RSVD-Pad23)") (class "Default")
      (node (ref "DD1") (pin "23") (pinfunction "RSVD_23") (pintype "power_in"))
      (node (ref "R22") (pin "2") (pinfunction "2_2") (pintype "passive"))
    )
    (net (code "36") (name "Net-(DD1-RSVD-Pad38)") (class "Default")
      (node (ref "DD1") (pin "38") (pinfunction "RSVD_38") (pintype "power_in"))
      (node (ref "R23") (pin "2") (pinfunction "2_2") (pintype "passive"))
    )
    (net (code "37") (name "Net-(DD1-RSVD-Pad39)") (class "Default")
      (node (ref "DD1") (pin "39") (pinfunction "RSVD_39") (pintype "power_in"))
      (node (ref "R24") (pin "2") (pinfunction "2_2") (pintype "passive"))
    )
    (net (code "38") (name "Net-(DD1-RSVD-Pad40)") (class "Default")
      (node (ref "DD1") (pin "40") (pinfunction "RSVD_40") (pintype "power_in"))
      (node (ref "R25") (pin "2") (pinfunction "2_2") (pintype "passive"))
    )
    (net (code "39") (name "Net-(DD1-RSVD-Pad41)") (class "Default")
      (node (ref "DD1") (pin "41") (pinfunction "RSVD_41") (pintype "power_in"))
      (node (ref "R26") (pin "2") (pinfunction "2_2") (pintype "passive"))
    )
    (net (code "40") (name "Net-(DD1-RSVD-Pad42)") (class "Default")
      (node (ref "DD1") (pin "42") (pinfunction "RSVD_42") (pintype "power_in"))
      (node (ref "R27") (pin "2") (pinfunction "2_2") (pintype "passive"))
    )
    (net (code "41") (name "Net-(DD1-TOCAP)") (class "Default")
      (node (ref "C19") (pin "1") (pinfunction "1_1") (pintype "passive"))
      (node (ref "DD1") (pin "20") (pinfunction "TOCAP_20") (pintype "power_in"))
    )
    (net (code "42") (name "Net-(DD1-XI{slash}CLKIN)") (class "Default")
      (node (ref "DD1") (pin "30") (pinfunction "XI/CLKIN_30") (pintype "power_in"))
      (node (ref "G1") (pin "3") (pinfunction "DCLK_3") (pintype "power_in"))
    )
    (net (code "43") (name "Net-(VD2-A)") (class "Default")
      (node (ref "C6") (pin "2") (pinfunction "2_2") (pintype "passive"))
      (node (ref "C7") (pin "2") (pinfunction "2_2") (pintype "passive"))
      (node (ref "L2") (pin "1") (pintype "passive"))
      (node (ref "VD2") (pin "2") (pinfunction "A_2") (pintype "passive"))
      (node (ref "X1") (pin "2") (pinfunction "2_2") (pintype "passive"))
      (node (ref "X1") (pin "4") (pinfunction "4_4") (pintype "passive"))
    )
    (net (code "44") (name "Net-(VD2-K)") (class "Default")
      (node (ref "C6") (pin "1") (pinfunction "1_1") (pintype "passive"))
      (node (ref "C7") (pin "1") (pinfunction "1_1") (pintype "passive"))
      (node (ref "L2") (pin "2") (pintype "passive"))
      (node (ref "VD2") (pin "1") (pinfunction "K_1") (pintype "passive"))
      (node (ref "X1") (pin "3") (pinfunction "3_3") (pintype "passive"))
    )
    (net (code "45") (name "Net-(X2-K1)") (class "Default")
      (node (ref "R18") (pin "1") (pinfunction "1_1") (pintype "passive"))
      (node (ref "X2") (pin "10") (pinfunction "K1_10") (pintype "passive"))
    )
    (net (code "46") (name "Net-(X2-K2)") (class "Default")
      (node (ref "R21") (pin "1") (pinfunction "1_1") (pintype "passive"))
      (node (ref "X2") (pin "11") (pinfunction "K2_11") (pintype "passive"))
    )
    (net (code "47") (name "Net-(X2-RCT)") (class "Default")
      (node (ref "C16") (pin "1") (pinfunction "1_1") (pintype "passive"))
      (node (ref "R4") (pin "1") (pinfunction "1_1") (pintype "passive"))
      (node (ref "R7") (pin "2") (pinfunction "2_2") (pintype "passive"))
      (node (ref "X2") (pin "5") (pinfunction "RCT_5") (pintype "passive"))
    )
    (net (code "48") (name "Net-(X2-TCT)") (class "Default")
      (node (ref "C18") (pin "1") (pinfunction "1_1") (pintype "passive"))
      (node (ref "R13") (pin "2") (pinfunction "2_2") (pintype "passive"))
      (node (ref "X2") (pin "4") (pinfunction "TCT_4") (pintype "passive"))
    )
    (net (code "49") (name "Net-(X2-TD+)") (class "Default")
      (node (ref "R14") (pin "2") (pinfunction "2_2") (pintype "passive"))
      (node (ref "X2") (pin "1") (pinfunction "TD+_1") (pintype "passive"))
    )
    (net (code "50") (name "Net-(X2-TD-)") (class "Default")
      (node (ref "R12") (pin "2") (pinfunction "2_2") (pintype "passive"))
      (node (ref "X2") (pin "2") (pinfunction "TD-_2") (pintype "passive"))
    )
    (net (code "51") (name "PGND") (class "Default")
      (node (ref "C10") (pin "1") (pinfunction "1_1") (pintype "passive"))
      (node (ref "C11") (pin "2") (pinfunction "2_2") (pintype "passive"))
      (node (ref "C12") (pin "2") (pinfunction "2_2") (pintype "passive"))
      (node (ref "C2") (pin "1") (pinfunction "1_1") (pintype "passive"))
      (node (ref "C3") (pin "1") (pinfunction "1_1") (pintype "passive"))
      (node (ref "C4") (pin "2") (pinfunction "2_2") (pintype "passive"))
      (node (ref "C5") (pin "2") (pinfunction "2_2") (pintype "passive"))
      (node (ref "C8") (pin "2") (pinfunction "2_2") (pintype "passive"))
      (node (ref "C9") (pin "1") (pinfunction "1_1") (pintype "passive"))
      (node (ref "DA1") (pin "4") (pinfunction "GND_4") (pintype "power_in"))
      (node (ref "DA2") (pin "4") (pinfunction "GND_4") (pintype "passive"))
      (node (ref "L2") (pin "3") (pintype "passive"))
      (node (ref "R2") (pin "2") (pinfunction "2_2") (pintype "passive"))
      (node (ref "R5") (pin "1") (pinfunction "1_1") (pintype "passive"))
      (node (ref "R6") (pin "1") (pinfunction "1_1") (pintype "passive"))
      (node (ref "VD1") (pin "2") (pinfunction "A_2") (pintype "passive"))
    )
    (net (code "52") (name "unconnected-(DD1-DNC-Pad7)") (class "Default")
      (node (ref "DD1") (pin "7") (pinfunction "DNC_7") (pintype "power_in+no_connect"))
    )
    (net (code "53") (name "unconnected-(DD1-DUPLED-Pad26)") (class "Default")
      (node (ref "DD1") (pin "26") (pinfunction "DUPLED_26") (pintype "power_in+no_connect"))
    )
    (net (code "54") (name "unconnected-(DD1-NC-Pad12)") (class "Default")
      (node (ref "DD1") (pin "12") (pinfunction "NC_12") (pintype "power_in+no_connect"))
    )
    (net (code "55") (name "unconnected-(DD1-NC-Pad13)") (class "Default")
      (node (ref "DD1") (pin "13") (pinfunction "NC_13") (pintype "power_in+no_connect"))
    )
    (net (code "56") (name "unconnected-(DD1-NC-Pad46)") (class "Default")
      (node (ref "DD1") (pin "46") (pinfunction "NC_46") (pintype "power_in+no_connect"))
    )
    (net (code "57") (name "unconnected-(DD1-NC-Pad47)") (class "Default")
      (node (ref "DD1") (pin "47") (pinfunction "NC_47") (pintype "power_in+no_connect"))
    )
    (net (code "58") (name "unconnected-(DD1-SPDLED-Pad24)") (class "Default")
      (node (ref "DD1") (pin "24") (pinfunction "SPDLED_24") (pintype "power_in+no_connect"))
    )
    (net (code "59") (name "unconnected-(DD1-VBG-Pad18)") (class "Default")
      (node (ref "DD1") (pin "18") (pinfunction "VBG_18") (pintype "power_in+no_connect"))
    )
    (net (code "60") (name "unconnected-(DD1-XO-Pad31)") (class "Default")
      (node (ref "DD1") (pin "31") (pinfunction "XO_31") (pintype "power_in+no_connect"))
    )
    (net (code "61") (name "unconnected-(G1-NC-Pad1)") (class "Default")
      (node (ref "G1") (pin "1") (pinfunction "NC_1") (pintype "power_in+no_connect"))
    )
    (net (code "62") (name "unconnected-(X2-A-Pad2)") (class "Default")
      (node (ref "X2") (pin "2") (pinfunction "A_2") (pintype "passive"))
    )
    (net (code "63") (name "unconnected-(X2-A-Pad2)_1") (class "Default")
      (node (ref "X2") (pin "2") (pinfunction "A_2") (pintype "passive"))
    )
    (net (code "64") (name "unconnected-(X2-K-Pad1)") (class "Default")
      (node (ref "X2") (pin "1") (pinfunction "K_1") (pintype "passive"))
    )
    (net (code "65") (name "unconnected-(X2-K-Pad1)_1") (class "Default")
      (node (ref "X2") (pin "1") (pinfunction "K_1") (pintype "passive"))
    )
    (net (code "66") (name "unconnected-(X2-NC-Pad7)") (class "Default")
      (node (ref "X2") (pin "7") (pinfunction "NC_7") (pintype "passive+no_connect"))
    )
    (net (code "67") (name "unconnected-(X2-Pad1)") (class "Default")
      (node (ref "X2") (pin "1") (pinfunction "1_1") (pintype "passive"))
    )
    (net (code "68") (name "unconnected-(X2-Pad1)_1") (class "Default")
      (node (ref "X2") (pin "1") (pinfunction "1_1") (pintype "passive"))
    )
    (net (code "69") (name "unconnected-(X2-Pad1)_2") (class "Default")
      (node (ref "X2") (pin "1") (pinfunction "1_1") (pintype "passive"))
    )
    (net (code "70") (name "unconnected-(X2-Pad1)_3") (class "Default")
      (node (ref "X2") (pin "1") (pinfunction "1_1") (pintype "passive"))
    )
    (net (code "71") (name "unconnected-(X2-Pad2)") (class "Default")
      (node (ref "X2") (pin "2") (pinfunction "2_2") (pintype "passive"))
    )
    (net (code "72") (name "unconnected-(X2-Pad2)_1") (class "Default")
      (node (ref "X2") (pin "2") (pinfunction "2_2") (pintype "passive"))
    )
    (net (code "73") (name "unconnected-(X2-Pad2)_2") (class "Default")
      (node (ref "X2") (pin "2") (pinfunction "2_2") (pintype "passive"))
    )
    (net (code "74") (name "unconnected-(X2-Pad2)_3") (class "Default")
      (node (ref "X2") (pin "2") (pinfunction "2_2") (pintype "passive"))
    )
  )
)
